# Main.net
KiCad netlist of a schematic drawn in Altium Designer
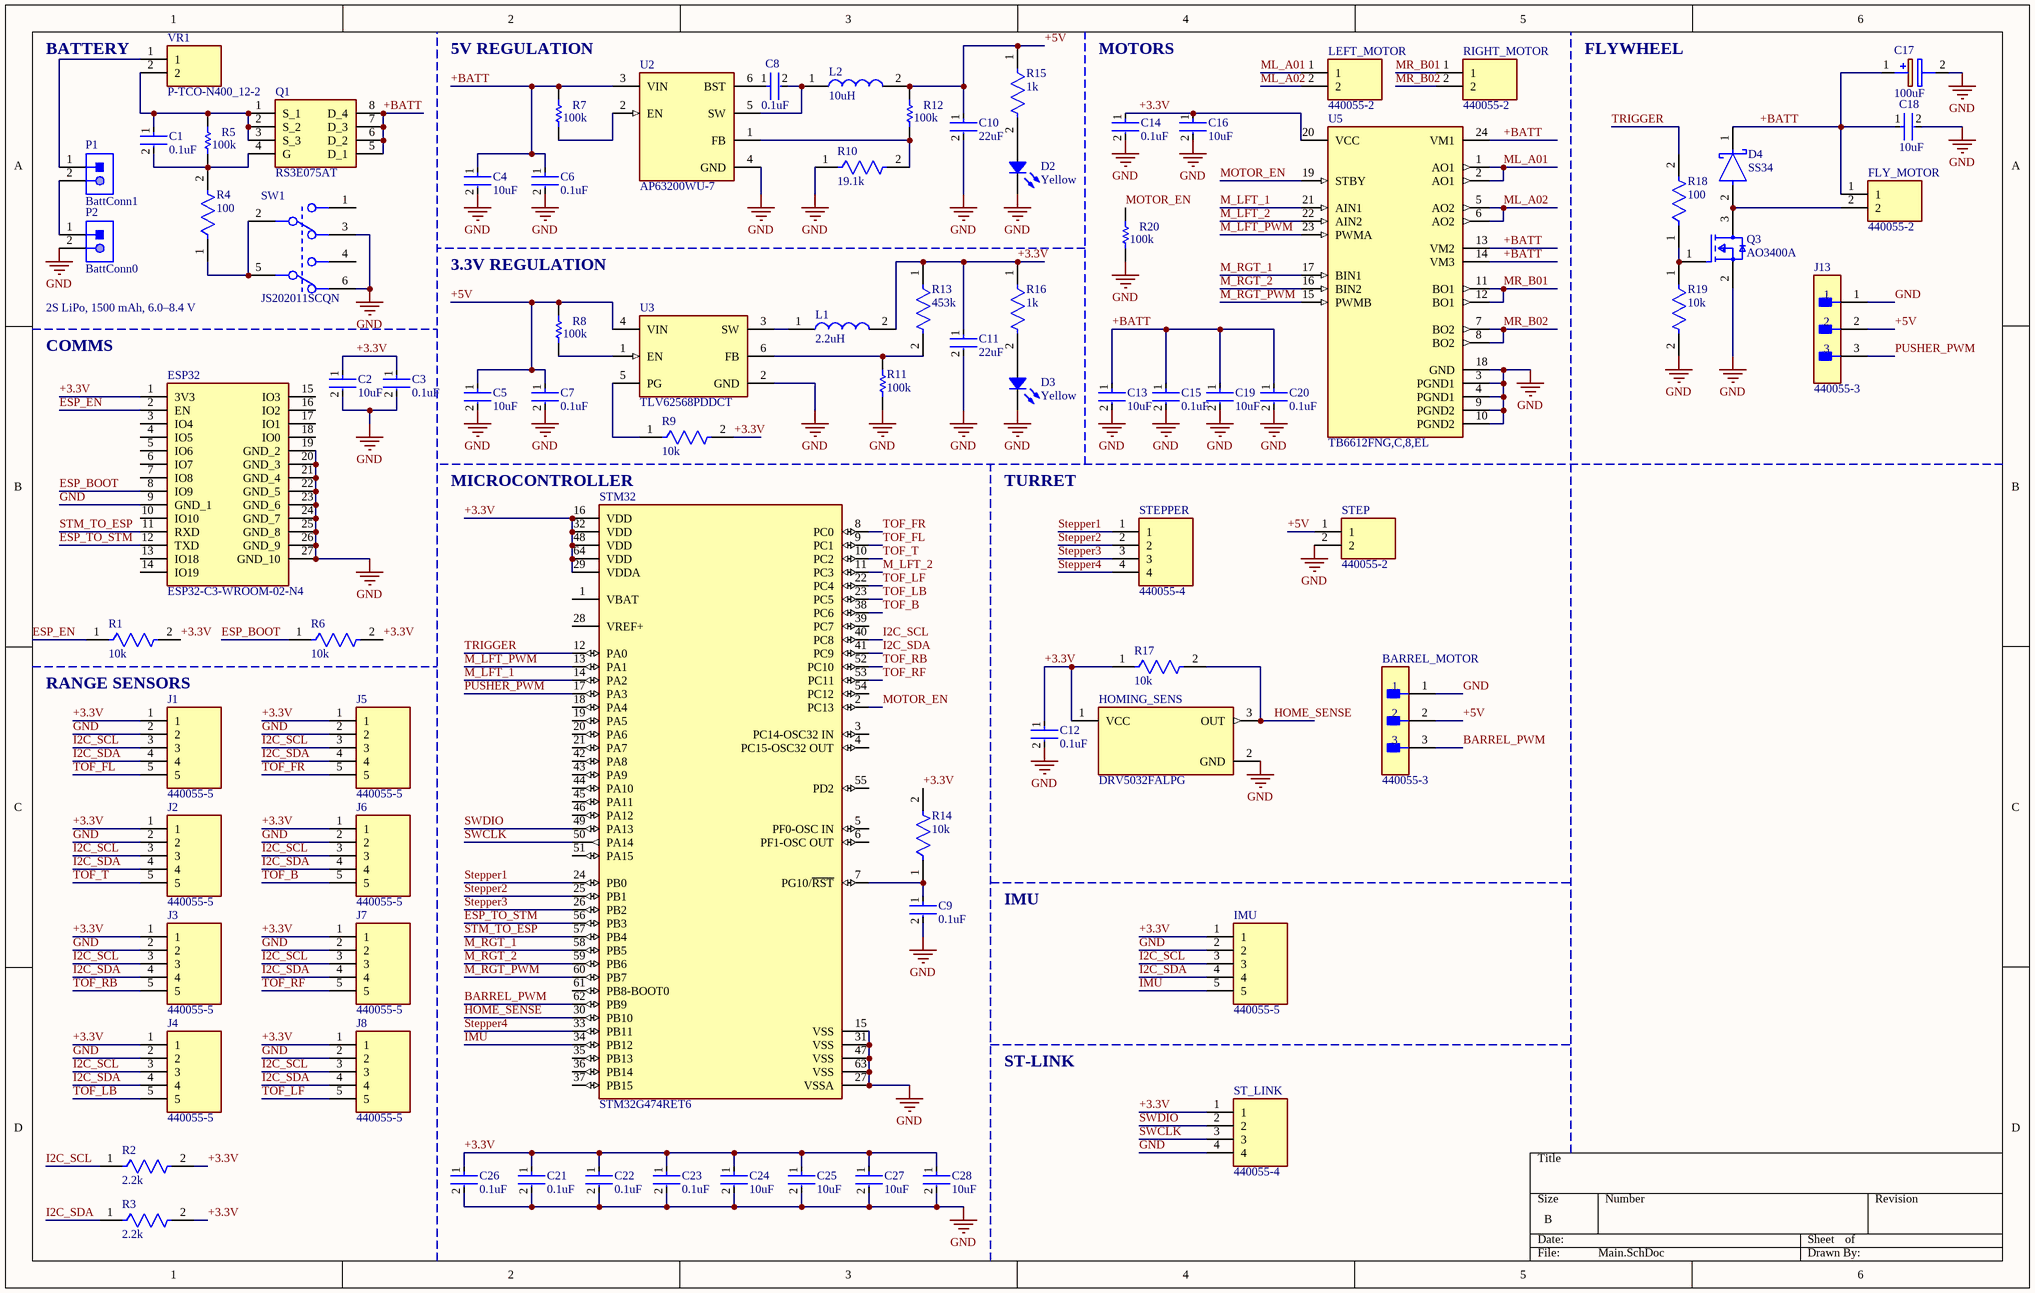
[diagram p0: Main.SchDoc]

(export (version "E")
  (design (tool "Eeschema 10.0.6"))
  (components
    (comp (ref "BARREL_MOTOR")
      (value "440055-3")
      (footprint "FP-440055-3-MFG")
      (description "CONN HEADER R/A 3POS 2MM")
      (fields
        (field (name "MANUFACTURER") "TE Connectivity")
        (field (name "OCTOPART") "https://octopart.com/440055-3-te+connectivity-40644627")
      )
      (libsource (lib "Altium Content Vault") (part "0d3f023dd272f625e17a2be33dea85f"))
    )
    (comp (ref "C1")
      (value "0.1uF")
      (footprint "FP-C0603C-CF-MFG")
      (fields
        (field (name "TOLERANCE") "0.01")
        (field (name "MANUFACTURER PART NUMBER") "C0603C101F1GACTU")
        (field (name "MANUFACTURER") "KEMET")
      )
      (libsource (lib "Altium Content Vault") (part "b4654b650e69147ec39a6b967a45e02"))
    )
    (comp (ref "C2")
      (value "10uF")
      (footprint "FP-GRM188-0_2-IPC_A")
      (description "Chip Multilayer Ceramic Capacitors for General Purpose, 0603, 10uF, X5R, 15%, 20%, 16V")
      (fields (field (name "TOLERANCE") "20%") (field (name "VOLTAGE") "16V"))
      (libsource (lib "Altium Content Vault") (part "11868f565c42a9108669ba33697ecf6"))
    )
    (comp (ref "C3")
      (value "0.1uF")
      (footprint "FP-C0603C-CF-MFG")
      (fields
        (field (name "TOLERANCE") "0.01")
        (field (name "MANUFACTURER PART NUMBER") "C0603C101F1GACTU")
        (field (name "MANUFACTURER") "KEMET")
      )
      (libsource (lib "Altium Content Vault") (part "b4654b650e69147ec39a6b967a45e02"))
    )
    (comp (ref "C4")
      (value "10uF")
      (footprint "FP-GRM188-0_2-IPC_A")
      (description "Chip Multilayer Ceramic Capacitors for General Purpose, 0603, 10uF, X5R, 15%, 20%, 16V")
      (fields (field (name "TOLERANCE") "20%") (field (name "VOLTAGE") "16V"))
      (libsource (lib "Altium Content Vault") (part "11868f565c42a9108669ba33697ecf6"))
    )
    (comp (ref "C5")
      (value "10uF")
      (footprint "FP-GRM188-0_2-IPC_A")
      (description "Chip Multilayer Ceramic Capacitors for General Purpose, 0603, 10uF, X5R, 15%, 20%, 16V")
      (fields (field (name "TOLERANCE") "20%") (field (name "VOLTAGE") "16V"))
      (libsource (lib "Altium Content Vault") (part "11868f565c42a9108669ba33697ecf6"))
    )
    (comp (ref "C6")
      (value "0.1uF")
      (footprint "FP-C0603C-CF-MFG")
      (fields
        (field (name "TOLERANCE") "0.01")
        (field (name "MANUFACTURER PART NUMBER") "C0603C101F1GACTU")
        (field (name "MANUFACTURER") "KEMET")
      )
      (libsource (lib "Altium Content Vault") (part "b4654b650e69147ec39a6b967a45e02"))
    )
    (comp (ref "C7")
      (value "0.1uF")
      (footprint "FP-C0603C-CF-MFG")
      (fields
        (field (name "TOLERANCE") "0.01")
        (field (name "MANUFACTURER PART NUMBER") "C0603C101F1GACTU")
        (field (name "MANUFACTURER") "KEMET")
      )
      (libsource (lib "Altium Content Vault") (part "b4654b650e69147ec39a6b967a45e02"))
    )
    (comp (ref "C8")
      (value "0.1uF")
      (footprint "FP-C0603C-CF-MFG")
      (fields
        (field (name "TOLERANCE") "0.01")
        (field (name "MANUFACTURER PART NUMBER") "C0603C101F1GACTU")
        (field (name "MANUFACTURER") "KEMET")
      )
      (libsource (lib "Altium Content Vault") (part "b4654b650e69147ec39a6b967a45e02"))
    )
    (comp (ref "C9")
      (value "0.1uF")
      (footprint "FP-C0603C-CF-MFG")
      (fields
        (field (name "TOLERANCE") "0.01")
        (field (name "MANUFACTURER PART NUMBER") "C0603C101F1GACTU")
        (field (name "MANUFACTURER") "KEMET")
      )
      (libsource (lib "Altium Content Vault") (part "b4654b650e69147ec39a6b967a45e02"))
    )
    (comp (ref "C10")
      (value "22uF")
      (footprint "FP-GRM188-0_2-IPC_A")
      (description "Multilayer Ceramic Capacitor 22uF 20% 16V X5R 0603 Paper T/R")
      (libsource (lib "Altium Content Vault") (part "02cd4be3c70576c341d710602a673aa"))
    )
    (comp (ref "C11")
      (value "22uF")
      (footprint "FP-GRM188-0_2-IPC_A")
      (description "Multilayer Ceramic Capacitor 22uF 20% 16V X5R 0603 Paper T/R")
      (libsource (lib "Altium Content Vault") (part "02cd4be3c70576c341d710602a673aa"))
    )
    (comp (ref "C12")
      (value "0.1uF")
      (footprint "FP-C0603C-CF-MFG")
      (fields
        (field (name "TOLERANCE") "0.01")
        (field (name "MANUFACTURER PART NUMBER") "C0603C101F1GACTU")
        (field (name "MANUFACTURER") "KEMET")
      )
      (libsource (lib "Altium Content Vault") (part "b4654b650e69147ec39a6b967a45e02"))
    )
    (comp (ref "C13")
      (value "10uF")
      (footprint "FP-GRM188-0_2-IPC_A")
      (description "Chip Multilayer Ceramic Capacitors for General Purpose, 0603, 10uF, X5R, 15%, 20%, 16V")
      (fields (field (name "TOLERANCE") "20%") (field (name "VOLTAGE") "16V"))
      (libsource (lib "Altium Content Vault") (part "11868f565c42a9108669ba33697ecf6"))
    )
    (comp (ref "C14")
      (value "0.1uF")
      (footprint "FP-C0603C-CF-MFG")
      (fields
        (field (name "TOLERANCE") "0.01")
        (field (name "MANUFACTURER PART NUMBER") "C0603C101F1GACTU")
        (field (name "MANUFACTURER") "KEMET")
      )
      (libsource (lib "Altium Content Vault") (part "b4654b650e69147ec39a6b967a45e02"))
    )
    (comp (ref "C15")
      (value "0.1uF")
      (footprint "FP-C0603C-CF-MFG")
      (fields
        (field (name "TOLERANCE") "0.01")
        (field (name "MANUFACTURER PART NUMBER") "C0603C101F1GACTU")
        (field (name "MANUFACTURER") "KEMET")
      )
      (libsource (lib "Altium Content Vault") (part "b4654b650e69147ec39a6b967a45e02"))
    )
    (comp (ref "C16")
      (value "10uF")
      (footprint "FP-GRM188-0_2-IPC_A")
      (description "Chip Multilayer Ceramic Capacitors for General Purpose, 0603, 10uF, X5R, 15%, 20%, 16V")
      (fields (field (name "TOLERANCE") "20%") (field (name "VOLTAGE") "16V"))
      (libsource (lib "Altium Content Vault") (part "11868f565c42a9108669ba33697ecf6"))
    )
    (comp (ref "C17")
      (value "100uF")
      (footprint "SamacSys:CAPPRD200W55D500H1250")
      (description "Capacitor Polarised")
      (fields
        (field (name "MANUFACTURER_PART_NUMBER") "EEU-FR1C101")
        (field (name "MOUSER PART NUMBER") "667-EEU-FR1C101")
      )
      (libsource (lib "*") (part "EEU-FR1C101"))
    )
    (comp (ref "C18")
      (value "10uF")
      (footprint "FP-GRM188-0_2-IPC_A")
      (description "Chip Multilayer Ceramic Capacitors for General Purpose, 0603, 10uF, X5R, 15%, 20%, 16V")
      (fields (field (name "TOLERANCE") "20%") (field (name "VOLTAGE") "16V"))
      (libsource (lib "Altium Content Vault") (part "11868f565c42a9108669ba33697ecf6"))
    )
    (comp (ref "C19")
      (value "10uF")
      (footprint "FP-GRM188-0_2-IPC_A")
      (description "Chip Multilayer Ceramic Capacitors for General Purpose, 0603, 10uF, X5R, 15%, 20%, 16V")
      (fields (field (name "TOLERANCE") "20%") (field (name "VOLTAGE") "16V"))
      (libsource (lib "Altium Content Vault") (part "11868f565c42a9108669ba33697ecf6"))
    )
    (comp (ref "C20")
      (value "0.1uF")
      (footprint "FP-C0603C-CF-MFG")
      (fields
        (field (name "TOLERANCE") "0.01")
        (field (name "MANUFACTURER PART NUMBER") "C0603C101F1GACTU")
        (field (name "MANUFACTURER") "KEMET")
      )
      (libsource (lib "Altium Content Vault") (part "b4654b650e69147ec39a6b967a45e02"))
    )
    (comp (ref "C21")
      (value "0.1uF")
      (footprint "FP-C0603C-CF-MFG")
      (fields
        (field (name "TOLERANCE") "0.01")
        (field (name "MANUFACTURER PART NUMBER") "C0603C101F1GACTU")
        (field (name "MANUFACTURER") "KEMET")
      )
      (libsource (lib "Altium Content Vault") (part "b4654b650e69147ec39a6b967a45e02"))
    )
    (comp (ref "C22")
      (value "0.1uF")
      (footprint "FP-C0603C-CF-MFG")
      (fields
        (field (name "TOLERANCE") "0.01")
        (field (name "MANUFACTURER PART NUMBER") "C0603C101F1GACTU")
        (field (name "MANUFACTURER") "KEMET")
      )
      (libsource (lib "Altium Content Vault") (part "b4654b650e69147ec39a6b967a45e02"))
    )
    (comp (ref "C23")
      (value "0.1uF")
      (footprint "FP-C0603C-CF-MFG")
      (fields
        (field (name "TOLERANCE") "0.01")
        (field (name "MANUFACTURER PART NUMBER") "C0603C101F1GACTU")
        (field (name "MANUFACTURER") "KEMET")
      )
      (libsource (lib "Altium Content Vault") (part "b4654b650e69147ec39a6b967a45e02"))
    )
    (comp (ref "C24")
      (value "10uF")
      (footprint "FP-GRM188-0_2-IPC_A")
      (description "Chip Multilayer Ceramic Capacitors for General Purpose, 0603, 10uF, X5R, 15%, 20%, 16V")
      (fields (field (name "TOLERANCE") "20%") (field (name "VOLTAGE") "16V"))
      (libsource (lib "Altium Content Vault") (part "11868f565c42a9108669ba33697ecf6"))
    )
    (comp (ref "C25")
      (value "10uF")
      (footprint "FP-GRM188-0_2-IPC_A")
      (description "Chip Multilayer Ceramic Capacitors for General Purpose, 0603, 10uF, X5R, 15%, 20%, 16V")
      (fields (field (name "TOLERANCE") "20%") (field (name "VOLTAGE") "16V"))
      (libsource (lib "Altium Content Vault") (part "11868f565c42a9108669ba33697ecf6"))
    )
    (comp (ref "C26")
      (value "0.1uF")
      (footprint "FP-C0603C-CF-MFG")
      (fields
        (field (name "TOLERANCE") "0.01")
        (field (name "MANUFACTURER PART NUMBER") "C0603C101F1GACTU")
        (field (name "MANUFACTURER") "KEMET")
      )
      (libsource (lib "Altium Content Vault") (part "b4654b650e69147ec39a6b967a45e02"))
    )
    (comp (ref "C27")
      (value "10uF")
      (footprint "FP-GRM188-0_2-IPC_A")
      (description "Chip Multilayer Ceramic Capacitors for General Purpose, 0603, 10uF, X5R, 15%, 20%, 16V")
      (fields (field (name "TOLERANCE") "20%") (field (name "VOLTAGE") "16V"))
      (libsource (lib "Altium Content Vault") (part "11868f565c42a9108669ba33697ecf6"))
    )
    (comp (ref "C28")
      (value "10uF")
      (footprint "FP-GRM188-0_2-IPC_A")
      (description "Chip Multilayer Ceramic Capacitors for General Purpose, 0603, 10uF, X5R, 15%, 20%, 16V")
      (fields (field (name "TOLERANCE") "20%") (field (name "VOLTAGE") "16V"))
      (libsource (lib "Altium Content Vault") (part "11868f565c42a9108669ba33697ecf6"))
    )
    (comp (ref "D2")
      (value "Yellow")
      (footprint "LED 1206_3216 YELLOW")
      (description "LED YELLOW CLEAR 2SMD")
      (fields
        (field (name "PART NUMBER") "25-21UYC/S530-A2/TR8")
        (field (name "MANUFACTURER") "Everlight Electronics Co Ltd")
      )
      (libsource (lib "Celestial Altium Library - altium_library") (part "LED"))
    )
    (comp (ref "D3")
      (value "Yellow")
      (footprint "LED 1206_3216 YELLOW")
      (description "LED YELLOW CLEAR 2SMD")
      (fields
        (field (name "PART NUMBER") "25-21UYC/S530-A2/TR8")
        (field (name "MANUFACTURER") "Everlight Electronics Co Ltd")
      )
      (libsource (lib "Celestial Altium Library - altium_library") (part "LED"))
    )
    (comp (ref "D4")
      (value "SS34")
      (footprint "FP-SMC-MFG")
      (description "DIODE SCHOTTKY 40V 3A DO214AB")
      (libsource (lib "Altium Content Vault") (part "c1678fac7984e62e0809fbf79c06691"))
    )
    (comp (ref "ESP32")
      (value "ESP32-C3-WROOM-02-N4")
      (footprint "SamacSys:ESP32C3WROOM02N4")
      (description "Integrated Circuit")
      (fields (field (name "MOUSER PART NUMBER") "356-ESP32C3WROOM02N4"))
      (libsource (lib "*") (part "ESP32-C3-WROOM-02-N4"))
    )
    (comp (ref "FLY_MOTOR")
      (value "440055-2")
      (footprint "SamacSys:SHDRRA2W50P0X200_1X2_600X770X525P")
      (description "Connector")
      (fields (field (name "MOUSER PART NUMBER") "571-440055-2"))
      (libsource (lib "*") (part "440055-2"))
    )
    (comp (ref "HOMING_SENS")
      (value "DRV5032FALPG")
      (footprint "FP-LPG0003A-MFG")
      (description "LP HALL 32 LPG")
      (libsource (lib "Altium Content Vault") (part "ff443a9f184bcdaea2d01bfae90e0ac"))
    )
    (comp (ref "IMU")
      (value "440055-5")
      (footprint "SamacSys:4400555")
      (description "Connector")
      (fields (field (name "MOUSER PART NUMBER") "571-440055-5"))
      (libsource (lib "*") (part "440055-5"))
    )
    (comp (ref "J1")
      (value "440055-5")
      (footprint "SamacSys:4400555")
      (description "Connector")
      (fields (field (name "MOUSER PART NUMBER") "571-440055-5"))
      (libsource (lib "*") (part "440055-5"))
    )
    (comp (ref "J2")
      (value "440055-5")
      (footprint "SamacSys:4400555")
      (description "Connector")
      (fields (field (name "MOUSER PART NUMBER") "571-440055-5"))
      (libsource (lib "*") (part "440055-5"))
    )
    (comp (ref "J3")
      (value "440055-5")
      (footprint "SamacSys:4400555")
      (description "Connector")
      (fields (field (name "MOUSER PART NUMBER") "571-440055-5"))
      (libsource (lib "*") (part "440055-5"))
    )
    (comp (ref "J4")
      (value "440055-5")
      (footprint "SamacSys:4400555")
      (description "Connector")
      (fields (field (name "MOUSER PART NUMBER") "571-440055-5"))
      (libsource (lib "*") (part "440055-5"))
    )
    (comp (ref "J5")
      (value "440055-5")
      (footprint "SamacSys:4400555")
      (description "Connector")
      (fields (field (name "MOUSER PART NUMBER") "571-440055-5"))
      (libsource (lib "*") (part "440055-5"))
    )
    (comp (ref "J6")
      (value "440055-5")
      (footprint "SamacSys:4400555")
      (description "Connector")
      (fields (field (name "MOUSER PART NUMBER") "571-440055-5"))
      (libsource (lib "*") (part "440055-5"))
    )
    (comp (ref "J7")
      (value "440055-5")
      (footprint "SamacSys:4400555")
      (description "Connector")
      (fields (field (name "MOUSER PART NUMBER") "571-440055-5"))
      (libsource (lib "*") (part "440055-5"))
    )
    (comp (ref "J8")
      (value "440055-5")
      (footprint "SamacSys:4400555")
      (description "Connector")
      (fields (field (name "MOUSER PART NUMBER") "571-440055-5"))
      (libsource (lib "*") (part "440055-5"))
    )
    (comp (ref "J13")
      (value "440055-3")
      (footprint "FP-440055-3-MFG")
      (description "CONN HEADER R/A 3POS 2MM")
      (fields
        (field (name "MANUFACTURER") "TE Connectivity")
        (field (name "OCTOPART") "https://octopart.com/440055-3-te+connectivity-40644627")
      )
      (libsource (lib "Altium Content Vault") (part "0d3f023dd272f625e17a2be33dea85f"))
    )
    (comp (ref "L1")
      (value "2.2uH")
      (footprint "SamacSys:VLS2520")
      (description "Inductor")
      (fields
        (field (name "MANUFACTURER_PART_NUMBER") "VLS252010HBX-2R2M-1")
        (field (name "MOUSER PART NUMBER") "810-VLS25201HBX2R2M1")
      )
      (libsource (lib "*") (part "VLS252010HBX-2R2M-1"))
    )
    (comp (ref "L2")
      (value "10uH")
      (footprint "SamacSys:VLS3012")
      (description "Inductor")
      (fields
        (field (name "MANUFACTURER_PART_NUMBER") "VLS3012CX-100M-1")
        (field (name "MOUSER PART NUMBER") "810-VLS3012CX-100M-1")
      )
      (libsource (lib "*") (part "VLS3012CX-100M-1"))
    )
    (comp (ref "LEFT_MOTOR")
      (value "440055-2")
      (footprint "SamacSys:SHDRRA2W50P0X200_1X2_600X770X525P")
      (description "Connector")
      (fields (field (name "MOUSER PART NUMBER") "571-440055-2"))
      (libsource (lib "*") (part "440055-2"))
    )
    (comp (ref "P1")
      (value "BattConn1")
      (footprint "JST-S2B-PH-K-S_V")
      (fields (field (name "TOLERANCE") "20%"))
      (libsource (lib "Altium Content Vault") (part "CN-1P-M-R2"))
    )
    (comp (ref "P2")
      (value "BattConn0")
      (footprint "JST-S2B-PH-K-S_V")
      (fields (field (name "TOLERANCE") "20%"))
      (libsource (lib "Altium Content Vault") (part "CN-1P-M-R2"))
    )
    (comp (ref "Q1")
      (value "RS3E075AT")
      (footprint "SamacSys:SOIC127P600X175-8N")
      (description "MOSFET (P-Channel)")
      (libsource (lib "*") (part "RS3E075AT"))
    )
    (comp (ref "Q3")
      (value "AO3400A")
      (footprint "FP-SOT23-MFG")
      (description "MOSFET N-CH 30V 5.7A SOT23")
      (libsource (lib "Altium Content Vault") (part "0a9ea7c96deaaede766a5b531c28de0"))
    )
    (comp (ref "R1")
      (value "10k")
      (footprint "FP-AC0603-IPC_A")
      (description "RES 10kΩ 5.00% 0.2W 0603")
      (libsource (lib "Altium Content Vault") (part "1029c3af85768c4190bb7ad29bc67b5"))
    )
    (comp (ref "R2")
      (value "2.2k")
      (footprint "FP-RT0603-MFG")
      (description "RT0603 2.2KΩ 0.1W 25 ppm/°C 0.50%")
      (fields
        (field (name "OCTOPART") "https://octopart.com/rt0603drd132k2l-yageo-91016345")
        (field (name "MANUFACTURER PART NUMBER") "RT0603DRD132K2L")
      )
      (libsource (lib "Altium Content Vault") (part "1029c3af85768c4190bb7ad29bc67b5"))
    )
    (comp (ref "R3")
      (value "2.2k")
      (footprint "FP-RT0603-MFG")
      (description "RT0603 2.2KΩ 0.1W 25 ppm/°C 0.50%")
      (fields
        (field (name "OCTOPART") "https://octopart.com/rt0603drd132k2l-yageo-91016345")
        (field (name "MANUFACTURER PART NUMBER") "RT0603DRD132K2L")
      )
      (libsource (lib "Altium Content Vault") (part "1029c3af85768c4190bb7ad29bc67b5"))
    )
    (comp (ref "R4")
      (value "100")
      (footprint "FP-RT0603-MFG")
      (description "RT0603 100Ω 0.1W 50 ppm/°C 1.00%")
      (fields (field (name "TOLERANCE") "0.01") (field (name "MANUFACTURER PART NUMBER") "RT0603FRE13100RL"))
      (libsource (lib "Altium Content Vault") (part "1029c3af85768c4190bb7ad29bc67b5"))
    )
    (comp (ref "R5")
      (value "100k")
      (footprint "RESC0603(1608)_N")
      (description "100K 0.1W 1% 0603 (1608 Metric)  SMD")
      (fields (field (name "POWER") "0.1 W") (field (name "TOLERANCE") "1 %"))
      (libsource (lib "Altium Content Vault") (part "RES"))
    )
    (comp (ref "R6")
      (value "10k")
      (footprint "FP-AC0603-IPC_A")
      (description "RES 10kΩ 5.00% 0.2W 0603")
      (libsource (lib "Altium Content Vault") (part "1029c3af85768c4190bb7ad29bc67b5"))
    )
    (comp (ref "R7")
      (value "100k")
      (footprint "RESC0603(1608)_N")
      (description "100K 0.1W 1% 0603 (1608 Metric)  SMD")
      (fields (field (name "POWER") "0.1 W") (field (name "TOLERANCE") "1 %"))
      (libsource (lib "Altium Content Vault") (part "RES"))
    )
    (comp (ref "R8")
      (value "100k")
      (footprint "RESC0603(1608)_N")
      (description "100K 0.1W 1% 0603 (1608 Metric)  SMD")
      (fields (field (name "POWER") "0.1 W") (field (name "TOLERANCE") "1 %"))
      (libsource (lib "Altium Content Vault") (part "RES"))
    )
    (comp (ref "R9")
      (value "10k")
      (footprint "FP-AC0603-IPC_A")
      (description "RES 10kΩ 5.00% 0.2W 0603")
      (libsource (lib "Altium Content Vault") (part "1029c3af85768c4190bb7ad29bc67b5"))
    )
    (comp (ref "R10")
      (value "19.1k")
      (footprint "FP-AC0603-MFG")
      (description "RES 19.1KΩ 1.00% 0.1W 0603")
      (fields (field (name "TOLERANCE") "1%"))
      (libsource (lib "Altium Content Vault") (part "1029c3af85768c4190bb7ad29bc67b5"))
    )
    (comp (ref "R11")
      (value "100k")
      (footprint "RESC0603(1608)_N")
      (description "100K 0.1W 1% 0603 (1608 Metric)  SMD")
      (fields (field (name "POWER") "0.1 W") (field (name "TOLERANCE") "1 %"))
      (libsource (lib "Altium Content Vault") (part "RES"))
    )
    (comp (ref "R12")
      (value "100k")
      (footprint "RESC0603(1608)_N")
      (description "100K 0.1W 1% 0603 (1608 Metric)  SMD")
      (fields (field (name "POWER") "0.1 W") (field (name "TOLERANCE") "1 %"))
      (libsource (lib "Altium Content Vault") (part "RES"))
    )
    (comp (ref "R13")
      (value "453k")
      (footprint "FP-MCT0603-IPC_B")
      (description "RES SMD 100 OHM 1% 1/8W 0603")
      (fields (field (name "TOLERANCE") "1%"))
      (libsource (lib "Altium Content Vault") (part "1029c3af85768c4190bb7ad29bc67b5"))
    )
    (comp (ref "R14")
      (value "10k")
      (footprint "FP-AC0603-IPC_A")
      (description "RES 10kΩ 5.00% 0.2W 0603")
      (libsource (lib "Altium Content Vault") (part "1029c3af85768c4190bb7ad29bc67b5"))
    )
    (comp (ref "R15")
      (value "1k")
      (footprint "FP-ERA3A-MFG")
      (description "ERA3ARW102V Res Thin Film 0603 1K Ohm 0.05% 0.1W ±10ppm/°C Molded SMD Punched Carrier T/R")
      (fields (field (name "TOLERANCE") "0.05%"))
      (libsource (lib "Altium Content Vault") (part "1029c3af85768c4190bb7ad29bc67b5"))
    )
    (comp (ref "R16")
      (value "1k")
      (footprint "FP-ERA3A-MFG")
      (description "ERA3ARW102V Res Thin Film 0603 1K Ohm 0.05% 0.1W ±10ppm/°C Molded SMD Punched Carrier T/R")
      (fields (field (name "TOLERANCE") "0.05%"))
      (libsource (lib "Altium Content Vault") (part "1029c3af85768c4190bb7ad29bc67b5"))
    )
    (comp (ref "R17")
      (value "10k")
      (footprint "FP-AC0603-IPC_A")
      (description "RES 10kΩ 5.00% 0.2W 0603")
      (libsource (lib "Altium Content Vault") (part "1029c3af85768c4190bb7ad29bc67b5"))
    )
    (comp (ref "R18")
      (value "100")
      (footprint "FP-RT0603-MFG")
      (description "RT0603 100Ω 0.1W 50 ppm/°C 1.00%")
      (fields (field (name "TOLERANCE") "0.01") (field (name "MANUFACTURER PART NUMBER") "RT0603FRE13100RL"))
      (libsource (lib "Altium Content Vault") (part "1029c3af85768c4190bb7ad29bc67b5"))
    )
    (comp (ref "R19")
      (value "10k")
      (footprint "FP-AC0603-IPC_A")
      (description "RES 10kΩ 5.00% 0.2W 0603")
      (libsource (lib "Altium Content Vault") (part "1029c3af85768c4190bb7ad29bc67b5"))
    )
    (comp (ref "R20")
      (value "100k")
      (footprint "RESC0603(1608)_N")
      (description "100K 0.1W 1% 0603 (1608 Metric)  SMD")
      (fields (field (name "POWER") "0.1 W") (field (name "TOLERANCE") "1 %"))
      (libsource (lib "Altium Content Vault") (part "RES"))
    )
    (comp (ref "RIGHT_MOTOR")
      (value "440055-2")
      (footprint "SamacSys:SHDRRA2W50P0X200_1X2_600X770X525P")
      (description "Connector")
      (fields (field (name "MOUSER PART NUMBER") "571-440055-2"))
      (libsource (lib "*") (part "440055-2"))
    )
    (comp (ref "STEP")
      (value "440055-2")
      (footprint "SamacSys:SHDRRA2W50P0X200_1X2_600X770X525P")
      (description "Connector")
      (fields (field (name "MOUSER PART NUMBER") "571-440055-2"))
      (libsource (lib "*") (part "440055-2"))
    )
    (comp (ref "STEPPER")
      (value "440055-4")
      (footprint "SamacSys:SHDRRA4W50P15X200_1X4_1000X770X525P")
      (description "Connector")
      (fields (field (name "MOUSER PART NUMBER") "571-440055-4"))
      (libsource (lib "*") (part "440055-4"))
    )
    (comp (ref "STM32")
      (value "STM32G474RET6")
      (footprint "FP-LQFP64-5W-MFG")
      (description "MAINSTREAM ARM CORTEX-M4 CORE WI")
      (fields
        (field (name "MANUFACTURER") "STMicroelectronics")
        (field (name "OCTOPART") "https://octopart.com/stm32g474ret6-stmicroelectronics-102308483")
      )
      (libsource (lib "Altium Content Vault") (part "f7e4c2ab6713028e27effac94efeea5"))
    )
    (comp (ref "ST_LINK")
      (value "440055-4")
      (footprint "SamacSys:SHDRRA4W50P15X200_1X4_1000X770X525P")
      (description "Connector")
      (fields (field (name "MOUSER PART NUMBER") "571-440055-4"))
      (libsource (lib "*") (part "440055-4"))
    )
    (comp (ref "SW1")
      (value "JS202011SCQN")
      (footprint "FP-JS202011SCQN-MFG")
      (description "SWITCH SLIDE DPDT 300MA 6V")
      (libsource (lib "Altium Content Vault") (part "ac99ea1af431c19115f5225061c5c88"))
    )
    (comp (ref "U2")
      (value "AP63200WU-7")
      (footprint "FP-TSOT26-MFG")
      (description "IC REG BUCK ADJUSTABLE 2A TSOT26")
      (fields
        (field (name "OCTOPART") "https://octopart.com/ap63200wu-7-diodes+inc.-98099548")
        (field (name "MANUFACTURER") "Diodes Inc.")
      )
      (libsource (lib "Altium Content Vault") (part "2ae3aed49e7ee94ca813948749813a1"))
    )
    (comp (ref "U3")
      (value "TLV62568PDDCT")
      (footprint "FP-DDC0006A-MFG")
      (description "IC REG BUCK ADJ 1A TSOT23-6")
      (libsource (lib "Altium Content Vault") (part "fcfae234c2e21ab116172289ae38564"))
    )
    (comp (ref "U5")
      (value "TB6612FNG,C,8,EL")
      (footprint "FP-SSOP24-P-300-0_65A-IPC_A")
      (description "IC MOTOR DRIVER 2.7V-5.5V 24SSOP")
      (libsource (lib "Altium Content Vault") (part "0e8a2fe7f3780dc9c50f4d41012bdec"))
    )
    (comp (ref "VR1")
      (value "P-TCO-N400_12-2")
      (footprint "SamacSys:THRMC3216X110N")
      (description "Variable Resistor")
      (fields
        (field (name "MANUFACTURER_PART_NUMBER") "P-TCO-N450/12-2")
        (field (name "MOUSER PART NUMBER") "652-P-TCO-N450/12-2")
      )
      (libsource (lib "*") (part "P-TCO-N450_12-2"))
    )
  )
  (nets
    (net (code "1") (name "/+3.3V") (class "Default")
      (node (ref "C11") (pin "1") (pinfunction "1_1") (pintype "passive"))
      (node (ref "C12") (pin "1") (pinfunction "1_1") (pintype "passive"))
      (node (ref "C14") (pin "1") (pinfunction "1_1") (pintype "passive"))
      (node (ref "C16") (pin "1") (pinfunction "1_1") (pintype "passive"))
      (node (ref "C2") (pin "1") (pinfunction "1_1") (pintype "passive"))
      (node (ref "C21") (pin "1") (pinfunction "1_1") (pintype "passive"))
      (node (ref "C22") (pin "1") (pinfunction "1_1") (pintype "passive"))
      (node (ref "C23") (pin "1") (pinfunction "1_1") (pintype "passive"))
      (node (ref "C24") (pin "1") (pinfunction "1_1") (pintype "passive"))
      (node (ref "C25") (pin "1") (pinfunction "1_1") (pintype "passive"))
      (node (ref "C26") (pin "1") (pinfunction "1_1") (pintype "passive"))
      (node (ref "C27") (pin "1") (pinfunction "1_1") (pintype "passive"))
      (node (ref "C28") (pin "1") (pinfunction "1_1") (pintype "passive"))
      (node (ref "C3") (pin "1") (pinfunction "1_1") (pintype "passive"))
      (node (ref "ESP32") (pin "1") (pinfunction "3V3_1") (pintype "passive"))
      (node (ref "HOMING_SENS") (pin "1") (pinfunction "VCC_1") (pintype "power_in"))
      (node (ref "IMU") (pin "1") (pinfunction "1_1") (pintype "passive"))
      (node (ref "J1") (pin "1") (pinfunction "1_1") (pintype "passive"))
      (node (ref "J2") (pin "1") (pinfunction "1_1") (pintype "passive"))
      (node (ref "J3") (pin "1") (pinfunction "1_1") (pintype "passive"))
      (node (ref "J4") (pin "1") (pinfunction "1_1") (pintype "passive"))
      (node (ref "J5") (pin "1") (pinfunction "1_1") (pintype "passive"))
      (node (ref "J6") (pin "1") (pinfunction "1_1") (pintype "passive"))
      (node (ref "J7") (pin "1") (pinfunction "1_1") (pintype "passive"))
      (node (ref "J8") (pin "1") (pinfunction "1_1") (pintype "passive"))
      (node (ref "L1") (pin "2") (pinfunction "2_2") (pintype "passive"))
      (node (ref "R1") (pin "2") (pinfunction "2_2") (pintype "passive"))
      (node (ref "R13") (pin "1") (pinfunction "1_1") (pintype "passive"))
      (node (ref "R14") (pin "2") (pinfunction "2_2") (pintype "passive"))
      (node (ref "R16") (pin "1") (pinfunction "1_1") (pintype "passive"))
      (node (ref "R17") (pin "1") (pinfunction "1_1") (pintype "passive"))
      (node (ref "R2") (pin "2") (pinfunction "2_2") (pintype "passive"))
      (node (ref "R3") (pin "2") (pinfunction "2_2") (pintype "passive"))
      (node (ref "R6") (pin "2") (pinfunction "2_2") (pintype "passive"))
      (node (ref "R9") (pin "2") (pinfunction "2_2") (pintype "passive"))
      (node (ref "STM32") (pin "16") (pinfunction "VDD_16") (pintype "power_in"))
      (node (ref "STM32") (pin "29") (pinfunction "VDDA_29") (pintype "power_in"))
      (node (ref "STM32") (pin "32") (pinfunction "VDD_32") (pintype "power_in"))
      (node (ref "STM32") (pin "48") (pinfunction "VDD_48") (pintype "power_in"))
      (node (ref "STM32") (pin "64") (pinfunction "VDD_64") (pintype "power_in"))
      (node (ref "ST_LINK") (pin "1") (pinfunction "1_1") (pintype "passive"))
      (node (ref "U5") (pin "20") (pinfunction "VCC_20") (pintype "power_in"))
    )
    (net (code "2") (name "/+5V") (class "Default")
      (node (ref "BARREL_MOTOR") (pin "2") (pinfunction "2_2") (pintype "passive"))
      (node (ref "C10") (pin "1") (pinfunction "1_1") (pintype "passive"))
      (node (ref "C5") (pin "1") (pinfunction "1_1") (pintype "passive"))
      (node (ref "C7") (pin "1") (pinfunction "1_1") (pintype "passive"))
      (node (ref "J13") (pin "2") (pinfunction "2_2") (pintype "passive"))
      (node (ref "L2") (pin "2") (pinfunction "2_2") (pintype "passive"))
      (node (ref "R12") (pin "2") (pinfunction "2_2") (pintype "passive"))
      (node (ref "R15") (pin "1") (pinfunction "1_1") (pintype "passive"))
      (node (ref "R8") (pin "2") (pinfunction "2_2") (pintype "passive"))
      (node (ref "STEP") (pin "1") (pinfunction "1_1") (pintype "passive"))
      (node (ref "U3") (pin "4") (pinfunction "VIN_4") (pintype "power_in"))
    )
    (net (code "3") (name "/+BATT") (class "Default")
      (node (ref "C13") (pin "1") (pinfunction "1_1") (pintype "passive"))
      (node (ref "C15") (pin "1") (pinfunction "1_1") (pintype "passive"))
      (node (ref "C17") (pin "1") (pinfunction "+_1") (pintype "passive"))
      (node (ref "C18") (pin "1") (pinfunction "1_1") (pintype "passive"))
      (node (ref "C19") (pin "1") (pinfunction "1_1") (pintype "passive"))
      (node (ref "C20") (pin "1") (pinfunction "1_1") (pintype "passive"))
      (node (ref "C4") (pin "1") (pinfunction "1_1") (pintype "passive"))
      (node (ref "C6") (pin "1") (pinfunction "1_1") (pintype "passive"))
      (node (ref "D4") (pin "1") (pinfunction "C_1") (pintype "passive"))
      (node (ref "FLY_MOTOR") (pin "1") (pinfunction "1_1") (pintype "passive"))
      (node (ref "Q1") (pin "5") (pinfunction "D_1_5") (pintype "passive"))
      (node (ref "Q1") (pin "6") (pinfunction "D_2_6") (pintype "passive"))
      (node (ref "Q1") (pin "7") (pinfunction "D_3_7") (pintype "passive"))
      (node (ref "Q1") (pin "8") (pinfunction "D_4_8") (pintype "passive"))
      (node (ref "R7") (pin "2") (pinfunction "2_2") (pintype "passive"))
      (node (ref "U2") (pin "3") (pinfunction "VIN_3") (pintype "power_in"))
      (node (ref "U5") (pin "13") (pinfunction "VM2_13") (pintype "power_in"))
      (node (ref "U5") (pin "14") (pinfunction "VM3_14") (pintype "power_in"))
      (node (ref "U5") (pin "24") (pinfunction "VM1_24") (pintype "power_in"))
    )
    (net (code "4") (name "/BARREL_PWM") (class "Default")
      (node (ref "BARREL_MOTOR") (pin "3") (pinfunction "3_3") (pintype "passive"))
      (node (ref "STM32") (pin "62") (pinfunction "PB9_62") (pintype "bidirectional"))
    )
    (net (code "5") (name "/ESP_BOOT") (class "Default")
      (node (ref "ESP32") (pin "8") (pinfunction "IO9_8") (pintype "passive"))
      (node (ref "R6") (pin "1") (pinfunction "1_1") (pintype "passive"))
    )
    (net (code "6") (name "/ESP_EN") (class "Default")
      (node (ref "ESP32") (pin "2") (pinfunction "EN_2") (pintype "passive"))
      (node (ref "R1") (pin "1") (pinfunction "1_1") (pintype "passive"))
    )
    (net (code "7") (name "/ESP_TO_STM") (class "Default")
      (node (ref "ESP32") (pin "12") (pinfunction "TXD_12") (pintype "passive"))
      (node (ref "STM32") (pin "56") (pinfunction "PB3_56") (pintype "bidirectional"))
    )
    (net (code "8") (name "/HOME_SENSE") (class "Default")
      (node (ref "HOMING_SENS") (pin "3") (pinfunction "OUT_3") (pintype "output"))
      (node (ref "R17") (pin "2") (pinfunction "2_2") (pintype "passive"))
      (node (ref "STM32") (pin "30") (pinfunction "PB10_30") (pintype "bidirectional"))
    )
    (net (code "9") (name "/I2C_SCL") (class "Default")
      (node (ref "IMU") (pin "3") (pinfunction "3_3") (pintype "passive"))
      (node (ref "J1") (pin "3") (pinfunction "3_3") (pintype "passive"))
      (node (ref "J2") (pin "3") (pinfunction "3_3") (pintype "passive"))
      (node (ref "J3") (pin "3") (pinfunction "3_3") (pintype "passive"))
      (node (ref "J4") (pin "3") (pinfunction "3_3") (pintype "passive"))
      (node (ref "J5") (pin "3") (pinfunction "3_3") (pintype "passive"))
      (node (ref "J6") (pin "3") (pinfunction "3_3") (pintype "passive"))
      (node (ref "J7") (pin "3") (pinfunction "3_3") (pintype "passive"))
      (node (ref "J8") (pin "3") (pinfunction "3_3") (pintype "passive"))
      (node (ref "R2") (pin "1") (pinfunction "1_1") (pintype "passive"))
      (node (ref "STM32") (pin "40") (pinfunction "PC8_40") (pintype "bidirectional"))
    )
    (net (code "10") (name "/I2C_SDA") (class "Default")
      (node (ref "IMU") (pin "4") (pinfunction "4_4") (pintype "passive"))
      (node (ref "J1") (pin "4") (pinfunction "4_4") (pintype "passive"))
      (node (ref "J2") (pin "4") (pinfunction "4_4") (pintype "passive"))
      (node (ref "J3") (pin "4") (pinfunction "4_4") (pintype "passive"))
      (node (ref "J4") (pin "4") (pinfunction "4_4") (pintype "passive"))
      (node (ref "J5") (pin "4") (pinfunction "4_4") (pintype "passive"))
      (node (ref "J6") (pin "4") (pinfunction "4_4") (pintype "passive"))
      (node (ref "J7") (pin "4") (pinfunction "4_4") (pintype "passive"))
      (node (ref "J8") (pin "4") (pinfunction "4_4") (pintype "passive"))
      (node (ref "R3") (pin "1") (pinfunction "1_1") (pintype "passive"))
      (node (ref "STM32") (pin "41") (pinfunction "PC9_41") (pintype "bidirectional"))
    )
    (net (code "11") (name "/IMU") (class "Default")
      (node (ref "IMU") (pin "5") (pinfunction "5_5") (pintype "passive"))
      (node (ref "STM32") (pin "34") (pinfunction "PB12_34") (pintype "bidirectional"))
    )
    (net (code "12") (name "/ML_A01") (class "Default")
      (node (ref "LEFT_MOTOR") (pin "1") (pinfunction "1_1") (pintype "passive"))
      (node (ref "U5") (pin "1") (pinfunction "AO1_1") (pintype "output"))
      (node (ref "U5") (pin "2") (pinfunction "AO1_2") (pintype "output"))
    )
    (net (code "13") (name "/ML_A02") (class "Default")
      (node (ref "LEFT_MOTOR") (pin "2") (pinfunction "2_2") (pintype "passive"))
      (node (ref "U5") (pin "5") (pinfunction "AO2_5") (pintype "output"))
      (node (ref "U5") (pin "6") (pinfunction "AO2_6") (pintype "output"))
    )
    (net (code "14") (name "/MOTOR_EN") (class "Default")
      (node (ref "R20") (pin "2") (pinfunction "2_2") (pintype "passive"))
      (node (ref "STM32") (pin "2") (pinfunction "PC13_2") (pintype "bidirectional"))
      (node (ref "U5") (pin "19") (pinfunction "STBY_19") (pintype "input"))
    )
    (net (code "15") (name "/MR_B01") (class "Default")
      (node (ref "RIGHT_MOTOR") (pin "1") (pinfunction "1_1") (pintype "passive"))
      (node (ref "U5") (pin "11") (pinfunction "BO1_11") (pintype "output"))
      (node (ref "U5") (pin "12") (pinfunction "BO1_12") (pintype "output"))
    )
    (net (code "16") (name "/MR_B02") (class "Default")
      (node (ref "RIGHT_MOTOR") (pin "2") (pinfunction "2_2") (pintype "passive"))
      (node (ref "U5") (pin "7") (pinfunction "BO2_7") (pintype "output"))
      (node (ref "U5") (pin "8") (pinfunction "BO2_8") (pintype "output"))
    )
    (net (code "17") (name "/M_LFT_1") (class "Default")
      (node (ref "STM32") (pin "14") (pinfunction "PA2_14") (pintype "bidirectional"))
      (node (ref "U5") (pin "21") (pinfunction "AIN1_21") (pintype "input"))
    )
    (net (code "18") (name "/M_LFT_2") (class "Default")
      (node (ref "STM32") (pin "11") (pinfunction "PC3_11") (pintype "bidirectional"))
      (node (ref "U5") (pin "22") (pinfunction "AIN2_22") (pintype "input"))
    )
    (net (code "19") (name "/M_LFT_PWM") (class "Default")
      (node (ref "STM32") (pin "13") (pinfunction "PA1_13") (pintype "bidirectional"))
      (node (ref "U5") (pin "23") (pinfunction "PWMA_23") (pintype "input"))
    )
    (net (code "20") (name "/M_RGT_1") (class "Default")
      (node (ref "STM32") (pin "58") (pinfunction "PB5_58") (pintype "bidirectional"))
      (node (ref "U5") (pin "17") (pinfunction "BIN1_17") (pintype "input"))
    )
    (net (code "21") (name "/M_RGT_2") (class "Default")
      (node (ref "STM32") (pin "59") (pinfunction "PB6_59") (pintype "bidirectional"))
      (node (ref "U5") (pin "16") (pinfunction "BIN2_16") (pintype "input"))
    )
    (net (code "22") (name "/M_RGT_PWM") (class "Default")
      (node (ref "STM32") (pin "60") (pinfunction "PB7_60") (pintype "bidirectional"))
      (node (ref "U5") (pin "15") (pinfunction "PWMB_15") (pintype "input"))
    )
    (net (code "23") (name "/PUSHER_PWM") (class "Default")
      (node (ref "J13") (pin "3") (pinfunction "3_3") (pintype "passive"))
      (node (ref "STM32") (pin "17") (pinfunction "PA3_17") (pintype "bidirectional"))
    )
    (net (code "24") (name "/STM_TO_ESP") (class "Default")
      (node (ref "ESP32") (pin "11") (pinfunction "RXD_11") (pintype "passive"))
      (node (ref "STM32") (pin "57") (pinfunction "PB4_57") (pintype "bidirectional"))
    )
    (net (code "25") (name "/SWCLK") (class "Default")
      (node (ref "STM32") (pin "50") (pinfunction "PA14_50") (pintype "output"))
      (node (ref "ST_LINK") (pin "3") (pinfunction "3_3") (pintype "passive"))
    )
    (net (code "26") (name "/SWDIO") (class "Default")
      (node (ref "STM32") (pin "49") (pinfunction "PA13_49") (pintype "bidirectional"))
      (node (ref "ST_LINK") (pin "2") (pinfunction "2_2") (pintype "passive"))
    )
    (net (code "27") (name "/Stepper1") (class "Default")
      (node (ref "STEPPER") (pin "1") (pinfunction "1_1") (pintype "passive"))
      (node (ref "STM32") (pin "24") (pinfunction "PB0_24") (pintype "bidirectional"))
    )
    (net (code "28") (name "/Stepper2") (class "Default")
      (node (ref "STEPPER") (pin "2") (pinfunction "2_2") (pintype "passive"))
      (node (ref "STM32") (pin "25") (pinfunction "PB1_25") (pintype "bidirectional"))
    )
    (net (code "29") (name "/Stepper3") (class "Default")
      (node (ref "STEPPER") (pin "3") (pinfunction "3_3") (pintype "passive"))
      (node (ref "STM32") (pin "26") (pinfunction "PB2_26") (pintype "bidirectional"))
    )
    (net (code "30") (name "/Stepper4") (class "Default")
      (node (ref "STEPPER") (pin "4") (pinfunction "4_4") (pintype "passive"))
      (node (ref "STM32") (pin "33") (pinfunction "PB11_33") (pintype "bidirectional"))
    )
    (net (code "31") (name "/TOF_B") (class "Default")
      (node (ref "J6") (pin "5") (pinfunction "5_5") (pintype "passive"))
      (node (ref "STM32") (pin "38") (pinfunction "PC6_38") (pintype "bidirectional"))
    )
    (net (code "32") (name "/TOF_FL") (class "Default")
      (node (ref "J1") (pin "5") (pinfunction "5_5") (pintype "passive"))
      (node (ref "STM32") (pin "9") (pinfunction "PC1_9") (pintype "bidirectional"))
    )
    (net (code "33") (name "/TOF_FR") (class "Default")
      (node (ref "J5") (pin "5") (pinfunction "5_5") (pintype "passive"))
      (node (ref "STM32") (pin "8") (pinfunction "PC0_8") (pintype "bidirectional"))
    )
    (net (code "34") (name "/TOF_LB") (class "Default")
      (node (ref "J4") (pin "5") (pinfunction "5_5") (pintype "passive"))
      (node (ref "STM32") (pin "23") (pinfunction "PC5_23") (pintype "bidirectional"))
    )
    (net (code "35") (name "/TOF_LF") (class "Default")
      (node (ref "J8") (pin "5") (pinfunction "5_5") (pintype "passive"))
      (node (ref "STM32") (pin "22") (pinfunction "PC4_22") (pintype "bidirectional"))
    )
    (net (code "36") (name "/TOF_RB") (class "Default")
      (node (ref "J3") (pin "5") (pinfunction "5_5") (pintype "passive"))
      (node (ref "STM32") (pin "52") (pinfunction "PC10_52") (pintype "bidirectional"))
    )
    (net (code "37") (name "/TOF_RF") (class "Default")
      (node (ref "J7") (pin "5") (pinfunction "5_5") (pintype "passive"))
      (node (ref "STM32") (pin "53") (pinfunction "PC11_53") (pintype "bidirectional"))
    )
    (net (code "38") (name "/TOF_T") (class "Default")
      (node (ref "J2") (pin "5") (pinfunction "5_5") (pintype "passive"))
      (node (ref "STM32") (pin "10") (pinfunction "PC2_10") (pintype "bidirectional"))
    )
    (net (code "39") (name "/TRIGGER") (class "Default")
      (node (ref "R18") (pin "2") (pinfunction "2_2") (pintype "passive"))
      (node (ref "STM32") (pin "12") (pinfunction "PA0_12") (pintype "bidirectional"))
    )
    (net (code "40") (name "GND") (class "Default")
      (node (ref "BARREL_MOTOR") (pin "1") (pinfunction "1_1") (pintype "passive"))
      (node (ref "C10") (pin "2") (pinfunction "2_2") (pintype "passive"))
      (node (ref "C11") (pin "2") (pinfunction "2_2") (pintype "passive"))
      (node (ref "C12") (pin "2") (pinfunction "2_2") (pintype "passive"))
      (node (ref "C13") (pin "2") (pinfunction "2_2") (pintype "passive"))
      (node (ref "C14") (pin "2") (pinfunction "2_2") (pintype "passive"))
      (node (ref "C15") (pin "2") (pinfunction "2_2") (pintype "passive"))
      (node (ref "C16") (pin "2") (pinfunction "2_2") (pintype "passive"))
      (node (ref "C17") (pin "2") (pinfunction "-_2") (pintype "passive"))
      (node (ref "C18") (pin "2") (pinfunction "2_2") (pintype "passive"))
      (node (ref "C19") (pin "2") (pinfunction "2_2") (pintype "passive"))
      (node (ref "C2") (pin "2") (pinfunction "2_2") (pintype "passive"))
      (node (ref "C20") (pin "2") (pinfunction "2_2") (pintype "passive"))
      (node (ref "C21") (pin "2") (pinfunction "2_2") (pintype "passive"))
      (node (ref "C22") (pin "2") (pinfunction "2_2") (pintype "passive"))
      (node (ref "C23") (pin "2") (pinfunction "2_2") (pintype "passive"))
      (node (ref "C24") (pin "2") (pinfunction "2_2") (pintype "passive"))
      (node (ref "C25") (pin "2") (pinfunction "2_2") (pintype "passive"))
      (node (ref "C26") (pin "2") (pinfunction "2_2") (pintype "passive"))
      (node (ref "C27") (pin "2") (pinfunction "2_2") (pintype "passive"))
      (node (ref "C28") (pin "2") (pinfunction "2_2") (pintype "passive"))
      (node (ref "C3") (pin "2") (pinfunction "2_2") (pintype "passive"))
      (node (ref "C4") (pin "2") (pinfunction "2_2") (pintype "passive"))
      (node (ref "C5") (pin "2") (pinfunction "2_2") (pintype "passive"))
      (node (ref "C6") (pin "2") (pinfunction "2_2") (pintype "passive"))
      (node (ref "C7") (pin "2") (pinfunction "2_2") (pintype "passive"))
      (node (ref "C9") (pin "2") (pinfunction "2_2") (pintype "passive"))
      (node (ref "D2") (pin "2") (pinfunction "2_2") (pintype "passive"))
      (node (ref "D3") (pin "2") (pinfunction "2_2") (pintype "passive"))
      (node (ref "ESP32") (pin "19") (pinfunction "GND_2_19") (pintype "passive"))
      (node (ref "ESP32") (pin "20") (pinfunction "GND_3_20") (pintype "passive"))
      (node (ref "ESP32") (pin "21") (pinfunction "GND_4_21") (pintype "passive"))
      (node (ref "ESP32") (pin "22") (pinfunction "GND_5_22") (pintype "passive"))
      (node (ref "ESP32") (pin "23") (pinfunction "GND_6_23") (pintype "passive"))
      (node (ref "ESP32") (pin "24") (pinfunction "GND_7_24") (pintype "passive"))
      (node (ref "ESP32") (pin "25") (pinfunction "GND_8_25") (pintype "passive"))
      (node (ref "ESP32") (pin "26") (pinfunction "GND_9_26") (pintype "passive"))
      (node (ref "ESP32") (pin "27") (pinfunction "GND_10_27") (pintype "passive"))
      (node (ref "ESP32") (pin "9") (pinfunction "GND_1_9") (pintype "passive"))
      (node (ref "HOMING_SENS") (pin "2") (pinfunction "GND_2") (pintype "power_in"))
      (node (ref "IMU") (pin "2") (pinfunction "2_2") (pintype "passive"))
      (node (ref "J1") (pin "2") (pinfunction "2_2") (pintype "passive"))
      (node (ref "J13") (pin "1") (pinfunction "1_1") (pintype "passive"))
      (node (ref "J2") (pin "2") (pinfunction "2_2") (pintype "passive"))
      (node (ref "J3") (pin "2") (pinfunction "2_2") (pintype "passive"))
      (node (ref "J4") (pin "2") (pinfunction "2_2") (pintype "passive"))
      (node (ref "J5") (pin "2") (pinfunction "2_2") (pintype "passive"))
      (node (ref "J6") (pin "2") (pinfunction "2_2") (pintype "passive"))
      (node (ref "J7") (pin "2") (pinfunction "2_2") (pintype "passive"))
      (node (ref "J8") (pin "2") (pinfunction "2_2") (pintype "passive"))
      (node (ref "P2") (pin "2") (pinfunction "2_2") (pintype "passive"))
      (node (ref "Q3") (pin "2") (pinfunction "S_2") (pintype "passive"))
      (node (ref "R10") (pin "1") (pinfunction "1_1") (pintype "passive"))
      (node (ref "R11") (pin "1") (pinfunction "1_1") (pintype "passive"))
      (node (ref "R19") (pin "2") (pinfunction "2_2") (pintype "passive"))
      (node (ref "R20") (pin "1") (pinfunction "1_1") (pintype "passive"))
      (node (ref "STEP") (pin "2") (pinfunction "2_2") (pintype "passive"))
      (node (ref "STM32") (pin "15") (pinfunction "VSS_15") (pintype "power_in"))
      (node (ref "STM32") (pin "27") (pinfunction "VSSA_27") (pintype "power_in"))
      (node (ref "STM32") (pin "31") (pinfunction "VSS_31") (pintype "power_in"))
      (node (ref "STM32") (pin "47") (pinfunction "VSS_47") (pintype "power_in"))
      (node (ref "STM32") (pin "63") (pinfunction "VSS_63") (pintype "power_in"))
      (node (ref "ST_LINK") (pin "4") (pinfunction "4_4") (pintype "passive"))
      (node (ref "SW1") (pin "3") (pinfunction "3_3") (pintype "passive"))
      (node (ref "SW1") (pin "6") (pinfunction "6_6") (pintype "passive"))
      (node (ref "U2") (pin "4") (pinfunction "GND_4") (pintype "power_in"))
      (node (ref "U3") (pin "2") (pinfunction "GND_2") (pintype "power_in"))
      (node (ref "U5") (pin "10") (pinfunction "PGND2_10") (pintype "power_in"))
      (node (ref "U5") (pin "18") (pinfunction "GND_18") (pintype "power_in"))
      (node (ref "U5") (pin "3") (pinfunction "PGND1_3") (pintype "power_in"))
      (node (ref "U5") (pin "4") (pinfunction "PGND1_4") (pintype "power_in"))
      (node (ref "U5") (pin "9") (pinfunction "PGND2_9") (pintype "power_in"))
    )
    (net (code "41") (name "Net-(D2-Pad1)") (class "Default")
      (node (ref "D2") (pin "1") (pinfunction "1_1") (pintype "passive"))
      (node (ref "R15") (pin "2") (pinfunction "2_2") (pintype "passive"))
    )
    (net (code "42") (name "Net-(D3-Pad1)") (class "Default")
      (node (ref "D3") (pin "1") (pinfunction "1_1") (pintype "passive"))
      (node (ref "R16") (pin "2") (pinfunction "2_2") (pintype "passive"))
    )
    (net (code "43") (name "Net-(D4-A)") (class "Default")
      (node (ref "D4") (pin "2") (pinfunction "A_2") (pintype "passive"))
      (node (ref "FLY_MOTOR") (pin "2") (pinfunction "2_2") (pintype "passive"))
      (node (ref "Q3") (pin "3") (pinfunction "D_3") (pintype "passive"))
    )
    (net (code "44") (name "Net-(P1-Pad1)") (class "Default")
      (node (ref "P1") (pin "1") (pinfunction "1_1") (pintype "passive"))
      (node (ref "VR1") (pin "1") (pinfunction "1_1") (pintype "passive"))
    )
    (net (code "45") (name "Net-(P1-Pad2)") (class "Default")
      (node (ref "P1") (pin "2") (pinfunction "2_2") (pintype "passive"))
      (node (ref "P2") (pin "1") (pinfunction "1_1") (pintype "passive"))
    )
    (net (code "46") (name "Net-(Q1-G)") (class "Default")
      (node (ref "C1") (pin "2") (pinfunction "2_2") (pintype "passive"))
      (node (ref "Q1") (pin "4") (pinfunction "G_4") (pintype "passive"))
      (node (ref "R4") (pin "2") (pinfunction "2_2") (pintype "passive"))
      (node (ref "R5") (pin "1") (pinfunction "1_1") (pintype "passive"))
    )
    (net (code "47") (name "Net-(Q1-S_1)") (class "Default")
      (node (ref "C1") (pin "1") (pinfunction "1_1") (pintype "passive"))
      (node (ref "Q1") (pin "1") (pinfunction "S_1_1") (pintype "passive"))
      (node (ref "Q1") (pin "2") (pinfunction "S_2_2") (pintype "passive"))
      (node (ref "Q1") (pin "3") (pinfunction "S_3_3") (pintype "passive"))
      (node (ref "R5") (pin "2") (pinfunction "2_2") (pintype "passive"))
      (node (ref "VR1") (pin "2") (pinfunction "2_2") (pintype "passive"))
    )
    (net (code "48") (name "Net-(Q3-G)") (class "Default")
      (node (ref "Q3") (pin "1") (pinfunction "G_1") (pintype "passive"))
      (node (ref "R18") (pin "1") (pinfunction "1_1") (pintype "passive"))
      (node (ref "R19") (pin "1") (pinfunction "1_1") (pintype "passive"))
    )
    (net (code "49") (name "Net-(R4-Pad1)") (class "Default")
      (node (ref "R4") (pin "1") (pinfunction "1_1") (pintype "passive"))
      (node (ref "SW1") (pin "2") (pinfunction "2_2") (pintype "passive"))
      (node (ref "SW1") (pin "5") (pinfunction "5_5") (pintype "passive"))
    )
    (net (code "50") (name "Net-(STM32-PG10{slash}~{RST})") (class "Default")
      (node (ref "C9") (pin "1") (pinfunction "1_1") (pintype "passive"))
      (node (ref "R14") (pin "1") (pinfunction "1_1") (pintype "passive"))
      (node (ref "STM32") (pin "7") (pinfunction "PG10/~{RST}_7") (pintype "bidirectional"))
    )
    (net (code "51") (name "Net-(U2-BST)") (class "Default")
      (node (ref "C8") (pin "1") (pinfunction "1_1") (pintype "passive"))
      (node (ref "U2") (pin "6") (pinfunction "BST_6") (pintype "passive"))
    )
    (net (code "52") (name "Net-(U2-EN)") (class "Default")
      (node (ref "R7") (pin "1") (pinfunction "1_1") (pintype "passive"))
      (node (ref "U2") (pin "2") (pinfunction "EN_2") (pintype "input"))
    )
    (net (code "53") (name "Net-(U2-FB)") (class "Default")
      (node (ref "R10") (pin "2") (pinfunction "2_2") (pintype "passive"))
      (node (ref "R12") (pin "1") (pinfunction "1_1") (pintype "passive"))
      (node (ref "U2") (pin "1") (pinfunction "FB_1") (pintype "passive"))
    )
    (net (code "54") (name "Net-(U2-SW)") (class "Default")
      (node (ref "C8") (pin "2") (pinfunction "2_2") (pintype "passive"))
      (node (ref "L2") (pin "1") (pinfunction "1_1") (pintype "passive"))
      (node (ref "U2") (pin "5") (pinfunction "SW_5") (pintype "passive"))
    )
    (net (code "55") (name "Net-(U3-EN)") (class "Default")
      (node (ref "R8") (pin "1") (pinfunction "1_1") (pintype "passive"))
      (node (ref "U3") (pin "1") (pinfunction "EN_1") (pintype "input"))
    )
    (net (code "56") (name "Net-(U3-FB)") (class "Default")
      (node (ref "R11") (pin "2") (pinfunction "2_2") (pintype "passive"))
      (node (ref "R13") (pin "2") (pinfunction "2_2") (pintype "passive"))
      (node (ref "U3") (pin "6") (pinfunction "FB_6") (pintype "passive"))
    )
    (net (code "57") (name "Net-(U3-PG)") (class "Default")
      (node (ref "R9") (pin "1") (pinfunction "1_1") (pintype "passive"))
      (node (ref "U3") (pin "5") (pinfunction "PG_5") (pintype "open_collector"))
    )
    (net (code "58") (name "Net-(U3-SW)") (class "Default")
      (node (ref "L1") (pin "1") (pinfunction "1_1") (pintype "passive"))
      (node (ref "U3") (pin "3") (pinfunction "SW_3") (pintype "passive"))
    )
    (net (code "59") (name "unconnected-(ESP32-IO0-Pad18)") (class "Default")
      (node (ref "ESP32") (pin "18") (pinfunction "IO0_18") (pintype "passive"))
    )
    (net (code "60") (name "unconnected-(ESP32-IO1-Pad17)") (class "Default")
      (node (ref "ESP32") (pin "17") (pinfunction "IO1_17") (pintype "passive"))
    )
    (net (code "61") (name "unconnected-(ESP32-IO2-Pad16)") (class "Default")
      (node (ref "ESP32") (pin "16") (pinfunction "IO2_16") (pintype "passive"))
    )
    (net (code "62") (name "unconnected-(ESP32-IO3-Pad15)") (class "Default")
      (node (ref "ESP32") (pin "15") (pinfunction "IO3_15") (pintype "passive"))
    )
    (net (code "63") (name "unconnected-(ESP32-IO4-Pad3)") (class "Default")
      (node (ref "ESP32") (pin "3") (pinfunction "IO4_3") (pintype "passive"))
    )
    (net (code "64") (name "unconnected-(ESP32-IO5-Pad4)") (class "Default")
      (node (ref "ESP32") (pin "4") (pinfunction "IO5_4") (pintype "passive"))
    )
    (net (code "65") (name "unconnected-(ESP32-IO6-Pad5)") (class "Default")
      (node (ref "ESP32") (pin "5") (pinfunction "IO6_5") (pintype "passive"))
    )
    (net (code "66") (name "unconnected-(ESP32-IO7-Pad6)") (class "Default")
      (node (ref "ESP32") (pin "6") (pinfunction "IO7_6") (pintype "passive"))
    )
    (net (code "67") (name "unconnected-(ESP32-IO8-Pad7)") (class "Default")
      (node (ref "ESP32") (pin "7") (pinfunction "IO8_7") (pintype "passive"))
    )
    (net (code "68") (name "unconnected-(ESP32-IO10-Pad10)") (class "Default")
      (node (ref "ESP32") (pin "10") (pinfunction "IO10_10") (pintype "passive"))
    )
    (net (code "69") (name "unconnected-(ESP32-IO18-Pad13)") (class "Default")
      (node (ref "ESP32") (pin "13") (pinfunction "IO18_13") (pintype "passive"))
    )
    (net (code "70") (name "unconnected-(ESP32-IO19-Pad14)") (class "Default")
      (node (ref "ESP32") (pin "14") (pinfunction "IO19_14") (pintype "passive"))
    )
    (net (code "71") (name "unconnected-(STM32-PA4-Pad18)") (class "Default")
      (node (ref "STM32") (pin "18") (pinfunction "PA4_18") (pintype "bidirectional"))
    )
    (net (code "72") (name "unconnected-(STM32-PA5-Pad19)") (class "Default")
      (node (ref "STM32") (pin "19") (pinfunction "PA5_19") (pintype "bidirectional"))
    )
    (net (code "73") (name "unconnected-(STM32-PA6-Pad20)") (class "Default")
      (node (ref "STM32") (pin "20") (pinfunction "PA6_20") (pintype "bidirectional"))
    )
    (net (code "74") (name "unconnected-(STM32-PA7-Pad21)") (class "Default")
      (node (ref "STM32") (pin "21") (pinfunction "PA7_21") (pintype "bidirectional"))
    )
    (net (code "75") (name "unconnected-(STM32-PA8-Pad42)") (class "Default")
      (node (ref "STM32") (pin "42") (pinfunction "PA8_42") (pintype "bidirectional"))
    )
    (net (code "76") (name "unconnected-(STM32-PA9-Pad43)") (class "Default")
      (node (ref "STM32") (pin "43") (pinfunction "PA9_43") (pintype "bidirectional"))
    )
    (net (code "77") (name "unconnected-(STM32-PA10-Pad44)") (class "Default")
      (node (ref "STM32") (pin "44") (pinfunction "PA10_44") (pintype "bidirectional"))
    )
    (net (code "78") (name "unconnected-(STM32-PA11-Pad45)") (class "Default")
      (node (ref "STM32") (pin "45") (pinfunction "PA11_45") (pintype "bidirectional"))
    )
    (net (code "79") (name "unconnected-(STM32-PA12-Pad46)") (class "Default")
      (node (ref "STM32") (pin "46") (pinfunction "PA12_46") (pintype "bidirectional"))
    )
    (net (code "80") (name "unconnected-(STM32-PA15-Pad51)") (class "Default")
      (node (ref "STM32") (pin "51") (pinfunction "PA15_51") (pintype "bidirectional"))
    )
    (net (code "81") (name "unconnected-(STM32-PB8-BOOT0-Pad61)") (class "Default")
      (node (ref "STM32") (pin "61") (pinfunction "PB8-BOOT0_61") (pintype "bidirectional"))
    )
    (net (code "82") (name "unconnected-(STM32-PB13-Pad35)") (class "Default")
      (node (ref "STM32") (pin "35") (pinfunction "PB13_35") (pintype "bidirectional"))
    )
    (net (code "83") (name "unconnected-(STM32-PB14-Pad36)") (class "Default")
      (node (ref "STM32") (pin "36") (pinfunction "PB14_36") (pintype "bidirectional"))
    )
    (net (code "84") (name "unconnected-(STM32-PB15-Pad37)") (class "Default")
      (node (ref "STM32") (pin "37") (pinfunction "PB15_37") (pintype "bidirectional"))
    )
    (net (code "85") (name "unconnected-(STM32-PC7-Pad39)") (class "Default")
      (node (ref "STM32") (pin "39") (pinfunction "PC7_39") (pintype "bidirectional"))
    )
    (net (code "86") (name "unconnected-(STM32-PC12-Pad54)") (class "Default")
      (node (ref "STM32") (pin "54") (pinfunction "PC12_54") (pintype "bidirectional"))
    )
    (net (code "87") (name "unconnected-(STM32-PC14-OSC32_IN-Pad3)") (class "Default")
      (node (ref "STM32") (pin "3") (pinfunction "PC14-OSC32_IN_3") (pintype "bidirectional"))
    )
    (net (code "88") (name "unconnected-(STM32-PC15-OSC32_OUT-Pad4)") (class "Default")
      (node (ref "STM32") (pin "4") (pinfunction "PC15-OSC32_OUT_4") (pintype "bidirectional"))
    )
    (net (code "89") (name "unconnected-(STM32-PD2-Pad55)") (class "Default")
      (node (ref "STM32") (pin "55") (pinfunction "PD2_55") (pintype "bidirectional"))
    )
    (net (code "90") (name "unconnected-(STM32-PF0-OSC_IN-Pad5)") (class "Default")
      (node (ref "STM32") (pin "5") (pinfunction "PF0-OSC_IN_5") (pintype "bidirectional"))
    )
    (net (code "91") (name "unconnected-(STM32-PF1-OSC_OUT-Pad6)") (class "Default")
      (node (ref "STM32") (pin "6") (pinfunction "PF1-OSC_OUT_6") (pintype "bidirectional"))
    )
    (net (code "92") (name "unconnected-(STM32-VBAT-Pad1)") (class "Default")
      (node (ref "STM32") (pin "1") (pinfunction "VBAT_1") (pintype "power_in"))
    )
    (net (code "93") (name "unconnected-(STM32-VREF+-Pad28)") (class "Default")
      (node (ref "STM32") (pin "28") (pinfunction "VREF+_28") (pintype "power_in"))
    )
    (net (code "94") (name "unconnected-(SW1-Pad1)") (class "Default")
      (node (ref "SW1") (pin "1") (pinfunction "1_1") (pintype "passive"))
    )
    (net (code "95") (name "unconnected-(SW1-Pad4)") (class "Default")
      (node (ref "SW1") (pin "4") (pinfunction "4_4") (pintype "passive"))
    )
  )
)
